# AutoFeatherPower2.net
KiCad netlist of a schematic drawn in EAGLE
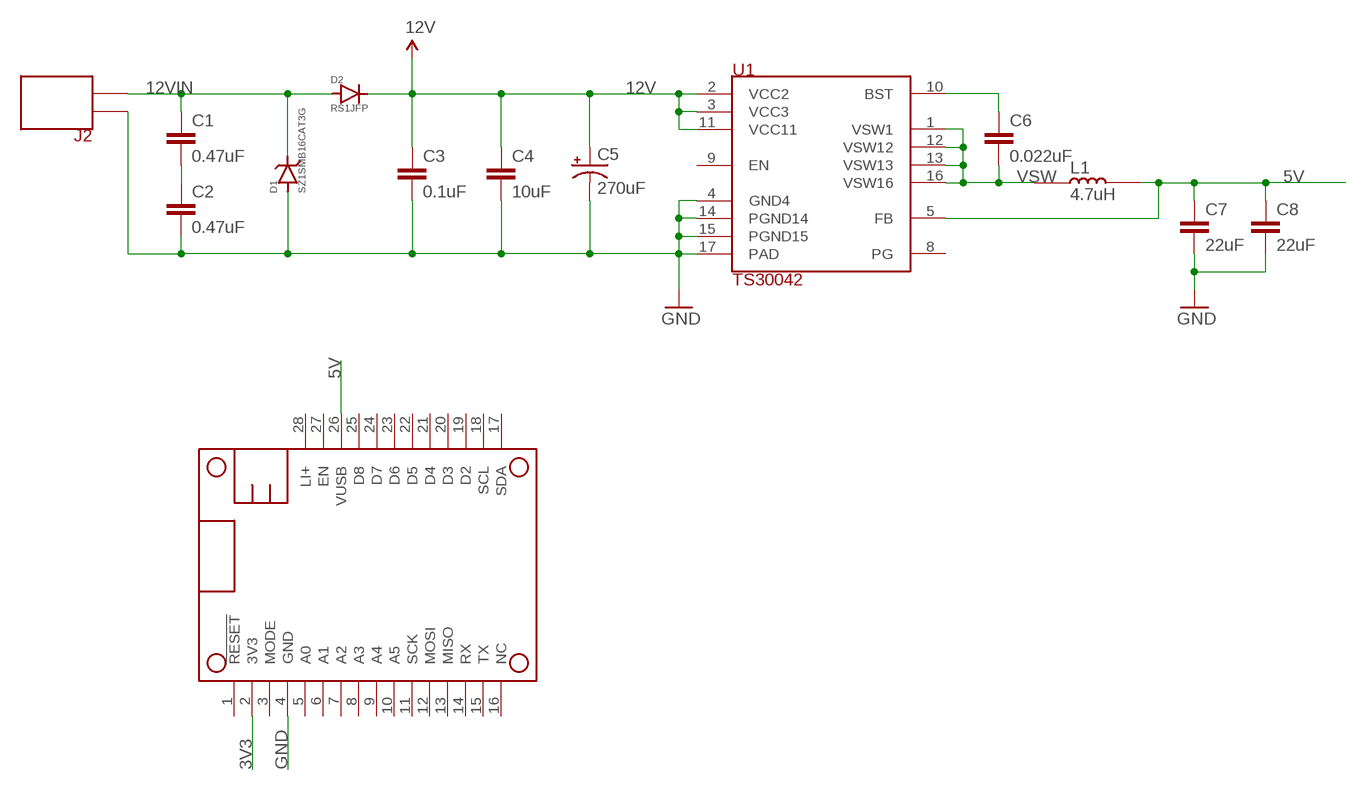
[diagram p0: schematic, sheet 1]

(export (version "E")
  (design (tool "Eeschema 10.0.6"))
  (components
    (comp (ref "C1")
      (value "0.47uF")
      (footprint "eagle-import:0805")
      (libsource (lib "eagle-import") (part "CAP-0.47UF-0805"))
    )
    (comp (ref "C2")
      (value "0.47uF")
      (footprint "eagle-import:0805")
      (libsource (lib "eagle-import") (part "CAP-0.47UF-0805"))
    )
    (comp (ref "C3")
      (value "0.1uF")
      (footprint "eagle-import:0603-CAP")
      (libsource (lib "eagle-import") (part "CAP-0.1UF-0603"))
    )
    (comp (ref "C4")
      (value "10uF")
      (footprint "eagle-import:0603-CAP")
      (libsource (lib "eagle-import") (part "CAP-10UF-0603"))
    )
    (comp (ref "C5")
      (value "270uF")
      (footprint "eagle-import:CAP-PANASONIC-FKS-V-F")
      (libsource (lib "eagle-import") (part "CAP-270UF-35V-SMD"))
    )
    (comp (ref "C6")
      (value "0.022uF")
      (footprint "eagle-import:0603-CAP")
      (libsource (lib "eagle-import") (part "CAP-0.022UF-0603"))
    )
    (comp (ref "C7")
      (value "22uF")
      (footprint "eagle-import:0805")
      (libsource (lib "eagle-import") (part "CAP-22UF-0805"))
    )
    (comp (ref "C8")
      (value "22uF")
      (footprint "eagle-import:0805")
      (libsource (lib "eagle-import") (part "CAP-22UF-0805"))
    )
    (comp (ref "D1")
      (value "SZ1SMB16CAT3G")
      (footprint "eagle-import:SZ1SMB")
      (libsource (lib "eagle-import") (part "DIODE-TVS-SZ1SMB"))
    )
    (comp (ref "D2")
      (value "RS1JFP")
      (footprint "eagle-import:SOD-123HE-ON")
      (libsource (lib "eagle-import") (part "DIODE-RS1JFP"))
    )
    (comp (ref "J2")
      (value "TERMBLOCK-2X3.5MM")
      (footprint "eagle-import:TERMBLOCK-2X3.5MM")
      (libsource (lib "eagle-import") (part "TERMBLOCK-2X3.5MM"))
    )
    (comp (ref "L1")
      (value "4.7uH")
      (footprint "eagle-import:WURTH-744774047")
      (libsource (lib "eagle-import") (part "INDUCTOR-4.7UH-3A"))
    )
    (comp (ref "MS1")
      (value "FEATHERWING_NODIM")
      (footprint "eagle-import:FEATHERWING_NODIM")
      (libsource (lib "eagle-import") (part "FEATHERWING_NODIM"))
    )
    (comp (ref "U1")
      (value "TS30042")
      (footprint "eagle-import:REG-TS30011")
      (libsource (lib "eagle-import") (part "REG-TS30011"))
    )
  )
  (nets
    (net (code "1") (name "/3V3") (class "Default")
      (node (ref "MS1") (pin "2") (pinfunction "3V3_2") (pintype "power_in"))
    )
    (net (code "2") (name "/5V") (class "Default")
      (node (ref "C7") (pin "1") (pinfunction "1_1") (pintype "passive"))
      (node (ref "C8") (pin "1") (pinfunction "1_1") (pintype "passive"))
      (node (ref "L1") (pin "2") (pinfunction "P$2_2") (pintype "passive"))
      (node (ref "MS1") (pin "26") (pinfunction "VUSB_26") (pintype "power_in"))
      (node (ref "U1") (pin "5") (pinfunction "FB_5") (pintype "passive"))
    )
    (net (code "3") (name "/12VIN") (class "Default")
      (node (ref "C1") (pin "1") (pinfunction "1_1") (pintype "passive"))
      (node (ref "D1") (pin "C") (pinfunction "CATHODE_C") (pintype "bidirectional"))
      (node (ref "D2") (pin "2") (pinfunction "ANODE_2") (pintype "bidirectional"))
      (node (ref "J2") (pin "2") (pinfunction "2_2") (pintype "passive"))
    )
    (net (code "4") (name "/LI+") (class "Default")
      (node (ref "MS1") (pin "28") (pinfunction "LI+_28") (pintype "power_in"))
    )
    (net (code "5") (name "/VSW") (class "Default")
      (node (ref "C6") (pin "2") (pinfunction "2_2") (pintype "passive"))
      (node (ref "L1") (pin "1") (pinfunction "P$1_1") (pintype "passive"))
      (node (ref "U1") (pin "1") (pinfunction "VSW1_1") (pintype "passive"))
      (node (ref "U1") (pin "12") (pinfunction "VSW12_12") (pintype "passive"))
      (node (ref "U1") (pin "13") (pinfunction "VSW13_13") (pintype "passive"))
      (node (ref "U1") (pin "16") (pinfunction "VSW16_16") (pintype "passive"))
    )
    (net (code "6") (name "12V") (class "Default")
      (node (ref "C3") (pin "1") (pinfunction "1_1") (pintype "passive"))
      (node (ref "C4") (pin "1") (pinfunction "1_1") (pintype "passive"))
      (node (ref "C5") (pin "P+") (pinfunction "+_P+") (pintype "passive"))
      (node (ref "D2") (pin "1") (pinfunction "CATHODE_1") (pintype "bidirectional"))
      (node (ref "U1") (pin "11") (pinfunction "VCC11_11") (pintype "power_in"))
      (node (ref "U1") (pin "2") (pinfunction "VCC2_2") (pintype "power_in"))
      (node (ref "U1") (pin "3") (pinfunction "VCC3_3") (pintype "power_in"))
    )
    (net (code "7") (name "GND") (class "Default")
      (node (ref "C2") (pin "2") (pinfunction "2_2") (pintype "passive"))
      (node (ref "C3") (pin "2") (pinfunction "2_2") (pintype "passive"))
      (node (ref "C4") (pin "2") (pinfunction "2_2") (pintype "passive"))
      (node (ref "C5") (pin "P-") (pinfunction "-_P-") (pintype "passive"))
      (node (ref "C7") (pin "2") (pinfunction "2_2") (pintype "passive"))
      (node (ref "C8") (pin "2") (pinfunction "2_2") (pintype "passive"))
      (node (ref "D1") (pin "A") (pinfunction "ANODE_A") (pintype "bidirectional"))
      (node (ref "J2") (pin "1") (pinfunction "1_1") (pintype "passive"))
      (node (ref "MS1") (pin "4") (pinfunction "GND_4") (pintype "power_in"))
      (node (ref "U1") (pin "14") (pinfunction "PGND14_14") (pintype "power_in"))
      (node (ref "U1") (pin "15") (pinfunction "PGND15_15") (pintype "power_in"))
      (node (ref "U1") (pin "17") (pinfunction "PAD_17") (pintype "power_in"))
      (node (ref "U1") (pin "4") (pinfunction "GND4_4") (pintype "power_in"))
    )
    (net (code "8") (name "Net-(C1-Pad2)") (class "Default")
      (node (ref "C1") (pin "2") (pinfunction "2_2") (pintype "passive"))
      (node (ref "C2") (pin "1") (pinfunction "1_1") (pintype "passive"))
    )
    (net (code "9") (name "Net-(U1-BST)") (class "Default")
      (node (ref "C6") (pin "1") (pinfunction "1_1") (pintype "passive"))
      (node (ref "U1") (pin "10") (pinfunction "BST_10") (pintype "passive"))
    )
    (net (code "10") (name "unconnected-(MS1-A0-Pad5)") (class "Default")
      (node (ref "MS1") (pin "5") (pinfunction "A0_5") (pintype "bidirectional"))
    )
    (net (code "11") (name "unconnected-(MS1-A1-Pad6)") (class "Default")
      (node (ref "MS1") (pin "6") (pinfunction "A1_6") (pintype "bidirectional"))
    )
    (net (code "12") (name "unconnected-(MS1-A2-Pad7)") (class "Default")
      (node (ref "MS1") (pin "7") (pinfunction "A2_7") (pintype "bidirectional"))
    )
    (net (code "13") (name "unconnected-(MS1-A3-Pad8)") (class "Default")
      (node (ref "MS1") (pin "8") (pinfunction "A3_8") (pintype "bidirectional"))
    )
    (net (code "14") (name "unconnected-(MS1-A4-Pad9)") (class "Default")
      (node (ref "MS1") (pin "9") (pinfunction "A4_9") (pintype "bidirectional"))
    )
    (net (code "15") (name "unconnected-(MS1-A5-Pad10)") (class "Default")
      (node (ref "MS1") (pin "10") (pinfunction "A5_10") (pintype "bidirectional"))
    )
    (net (code "16") (name "unconnected-(MS1-D2-Pad19)") (class "Default")
      (node (ref "MS1") (pin "19") (pinfunction "D2_19") (pintype "bidirectional"))
    )
    (net (code "17") (name "unconnected-(MS1-D3-Pad20)") (class "Default")
      (node (ref "MS1") (pin "20") (pinfunction "D3_20") (pintype "bidirectional"))
    )
    (net (code "18") (name "unconnected-(MS1-D4-Pad21)") (class "Default")
      (node (ref "MS1") (pin "21") (pinfunction "D4_21") (pintype "bidirectional"))
    )
    (net (code "19") (name "unconnected-(MS1-D5-Pad22)") (class "Default")
      (node (ref "MS1") (pin "22") (pinfunction "D5_22") (pintype "bidirectional"))
    )
    (net (code "20") (name "unconnected-(MS1-D6-Pad23)") (class "Default")
      (node (ref "MS1") (pin "23") (pinfunction "D6_23") (pintype "bidirectional"))
    )
    (net (code "21") (name "unconnected-(MS1-D7-Pad24)") (class "Default")
      (node (ref "MS1") (pin "24") (pinfunction "D7_24") (pintype "bidirectional"))
    )
    (net (code "22") (name "unconnected-(MS1-D8-Pad25)") (class "Default")
      (node (ref "MS1") (pin "25") (pinfunction "D8_25") (pintype "bidirectional"))
    )
    (net (code "23") (name "unconnected-(MS1-EN-Pad27)") (class "Default")
      (node (ref "MS1") (pin "27") (pinfunction "EN_27") (pintype "passive"))
    )
    (net (code "24") (name "unconnected-(MS1-MISO-Pad13)") (class "Default")
      (node (ref "MS1") (pin "13") (pinfunction "MISO_13") (pintype "bidirectional"))
    )
    (net (code "25") (name "unconnected-(MS1-MODE-Pad3)") (class "Default")
      (node (ref "MS1") (pin "3") (pinfunction "MODE_3") (pintype "passive"))
    )
    (net (code "26") (name "unconnected-(MS1-MOSI-Pad12)") (class "Default")
      (node (ref "MS1") (pin "12") (pinfunction "MOSI_12") (pintype "bidirectional"))
    )
    (net (code "27") (name "unconnected-(MS1-NC-Pad16)") (class "Default")
      (node (ref "MS1") (pin "16") (pinfunction "NC_16") (pintype "passive"))
    )
    (net (code "28") (name "unconnected-(MS1-RX-Pad14)") (class "Default")
      (node (ref "MS1") (pin "14") (pinfunction "RX_14") (pintype "bidirectional"))
    )
    (net (code "29") (name "unconnected-(MS1-SCK-Pad11)") (class "Default")
      (node (ref "MS1") (pin "11") (pinfunction "SCK_11") (pintype "bidirectional"))
    )
    (net (code "30") (name "unconnected-(MS1-SCL-Pad18)") (class "Default")
      (node (ref "MS1") (pin "18") (pinfunction "SCL_18") (pintype "bidirectional"))
    )
    (net (code "31") (name "unconnected-(MS1-SDA-Pad17)") (class "Default")
      (node (ref "MS1") (pin "17") (pinfunction "SDA_17") (pintype "bidirectional"))
    )
    (net (code "32") (name "unconnected-(MS1-TX-Pad15)") (class "Default")
      (node (ref "MS1") (pin "15") (pinfunction "TX_15") (pintype "bidirectional"))
    )
    (net (code "33") (name "unconnected-(MS1-~{RESET}-Pad1)") (class "Default")
      (node (ref "MS1") (pin "1") (pinfunction "~{RESET}_1") (pintype "input"))
    )
    (net (code "34") (name "unconnected-(U1-EN-Pad9)") (class "Default")
      (node (ref "U1") (pin "9") (pinfunction "EN_9") (pintype "input"))
    )
    (net (code "35") (name "unconnected-(U1-PG-Pad8)") (class "Default")
      (node (ref "U1") (pin "8") (pinfunction "PG_8") (pintype "output"))
    )
  )
)
